# Nusbio1_0_WaveShare.net
KiCad netlist of a schematic drawn in EAGLE
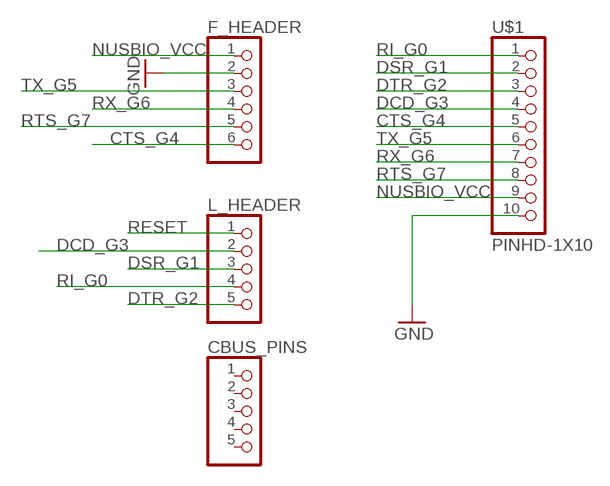
[diagram p0: schematic, sheet 1]

(export (version "E")
  (design (tool "Eeschema 10.0.6"))
  (components
    (comp (ref "CBUS_PINS")
      (value "PINHD-1X5")
      (footprint "eagle-import:1X05")
      (libsource (lib "eagle-import") (part "PINHD-1X5"))
    )
    (comp (ref "F_HEADER")
      (value "PINHD-1X6")
      (footprint "eagle-import:1X06")
      (libsource (lib "eagle-import") (part "PINHD-1X6"))
    )
    (comp (ref "L_HEADER")
      (value "PINHD-1X5")
      (footprint "eagle-import:1X05")
      (libsource (lib "eagle-import") (part "PINHD-1X5"))
    )
    (comp (ref "U$1")
      (value "PINHD-1X10")
      (footprint "eagle-import:1X10-BIG")
      (libsource (lib "eagle-import") (part "PINHD-1X10"))
    )
  )
  (nets
    (net (code "1") (name "/CTS_G4") (class "Default")
      (node (ref "F_HEADER") (pin "6") (pinfunction "6_6") (pintype "passive"))
      (node (ref "U$1") (pin "5") (pinfunction "5_5") (pintype "passive"))
    )
    (net (code "2") (name "/DCD_G3") (class "Default")
      (node (ref "L_HEADER") (pin "2") (pinfunction "2_2") (pintype "passive"))
      (node (ref "U$1") (pin "4") (pinfunction "4_4") (pintype "passive"))
    )
    (net (code "3") (name "/DSR_G1") (class "Default")
      (node (ref "L_HEADER") (pin "3") (pinfunction "3_3") (pintype "passive"))
      (node (ref "U$1") (pin "2") (pinfunction "2_2") (pintype "passive"))
    )
    (net (code "4") (name "/DTR_G2") (class "Default")
      (node (ref "L_HEADER") (pin "5") (pinfunction "5_5") (pintype "passive"))
      (node (ref "U$1") (pin "3") (pinfunction "3_3") (pintype "passive"))
    )
    (net (code "5") (name "/NUSBIO_VCC") (class "Default")
      (node (ref "F_HEADER") (pin "1") (pinfunction "1_1") (pintype "passive"))
      (node (ref "U$1") (pin "9") (pinfunction "9_9") (pintype "passive"))
    )
    (net (code "6") (name "/RESET") (class "Default")
      (node (ref "L_HEADER") (pin "1") (pinfunction "1_1") (pintype "passive"))
    )
    (net (code "7") (name "/RI_G0") (class "Default")
      (node (ref "L_HEADER") (pin "4") (pinfunction "4_4") (pintype "passive"))
      (node (ref "U$1") (pin "1") (pinfunction "1_1") (pintype "passive"))
    )
    (net (code "8") (name "/RTS_G7") (class "Default")
      (node (ref "F_HEADER") (pin "5") (pinfunction "5_5") (pintype "passive"))
      (node (ref "U$1") (pin "8") (pinfunction "8_8") (pintype "passive"))
    )
    (net (code "9") (name "/RX_G6") (class "Default")
      (node (ref "F_HEADER") (pin "4") (pinfunction "4_4") (pintype "passive"))
      (node (ref "U$1") (pin "7") (pinfunction "7_7") (pintype "passive"))
    )
    (net (code "10") (name "/TX_G5") (class "Default")
      (node (ref "F_HEADER") (pin "3") (pinfunction "3_3") (pintype "passive"))
      (node (ref "U$1") (pin "6") (pinfunction "6_6") (pintype "passive"))
    )
    (net (code "11") (name "GND") (class "Default")
      (node (ref "F_HEADER") (pin "2") (pinfunction "2_2") (pintype "passive"))
      (node (ref "U$1") (pin "10") (pinfunction "10_10") (pintype "passive"))
    )
    (net (code "12") (name "unconnected-(CBUS_PINS-Pad1)") (class "Default")
      (node (ref "CBUS_PINS") (pin "1") (pinfunction "1_1") (pintype "passive"))
    )
    (net (code "13") (name "unconnected-(CBUS_PINS-Pad2)") (class "Default")
      (node (ref "CBUS_PINS") (pin "2") (pinfunction "2_2") (pintype "passive"))
    )
    (net (code "14") (name "unconnected-(CBUS_PINS-Pad3)") (class "Default")
      (node (ref "CBUS_PINS") (pin "3") (pinfunction "3_3") (pintype "passive"))
    )
    (net (code "15") (name "unconnected-(CBUS_PINS-Pad4)") (class "Default")
      (node (ref "CBUS_PINS") (pin "4") (pinfunction "4_4") (pintype "passive"))
    )
    (net (code "16") (name "unconnected-(CBUS_PINS-Pad5)") (class "Default")
      (node (ref "CBUS_PINS") (pin "5") (pinfunction "5_5") (pintype "passive"))
    )
  )
)
